# design.net
KiCad netlist of a schematic drawn in Altium Designer
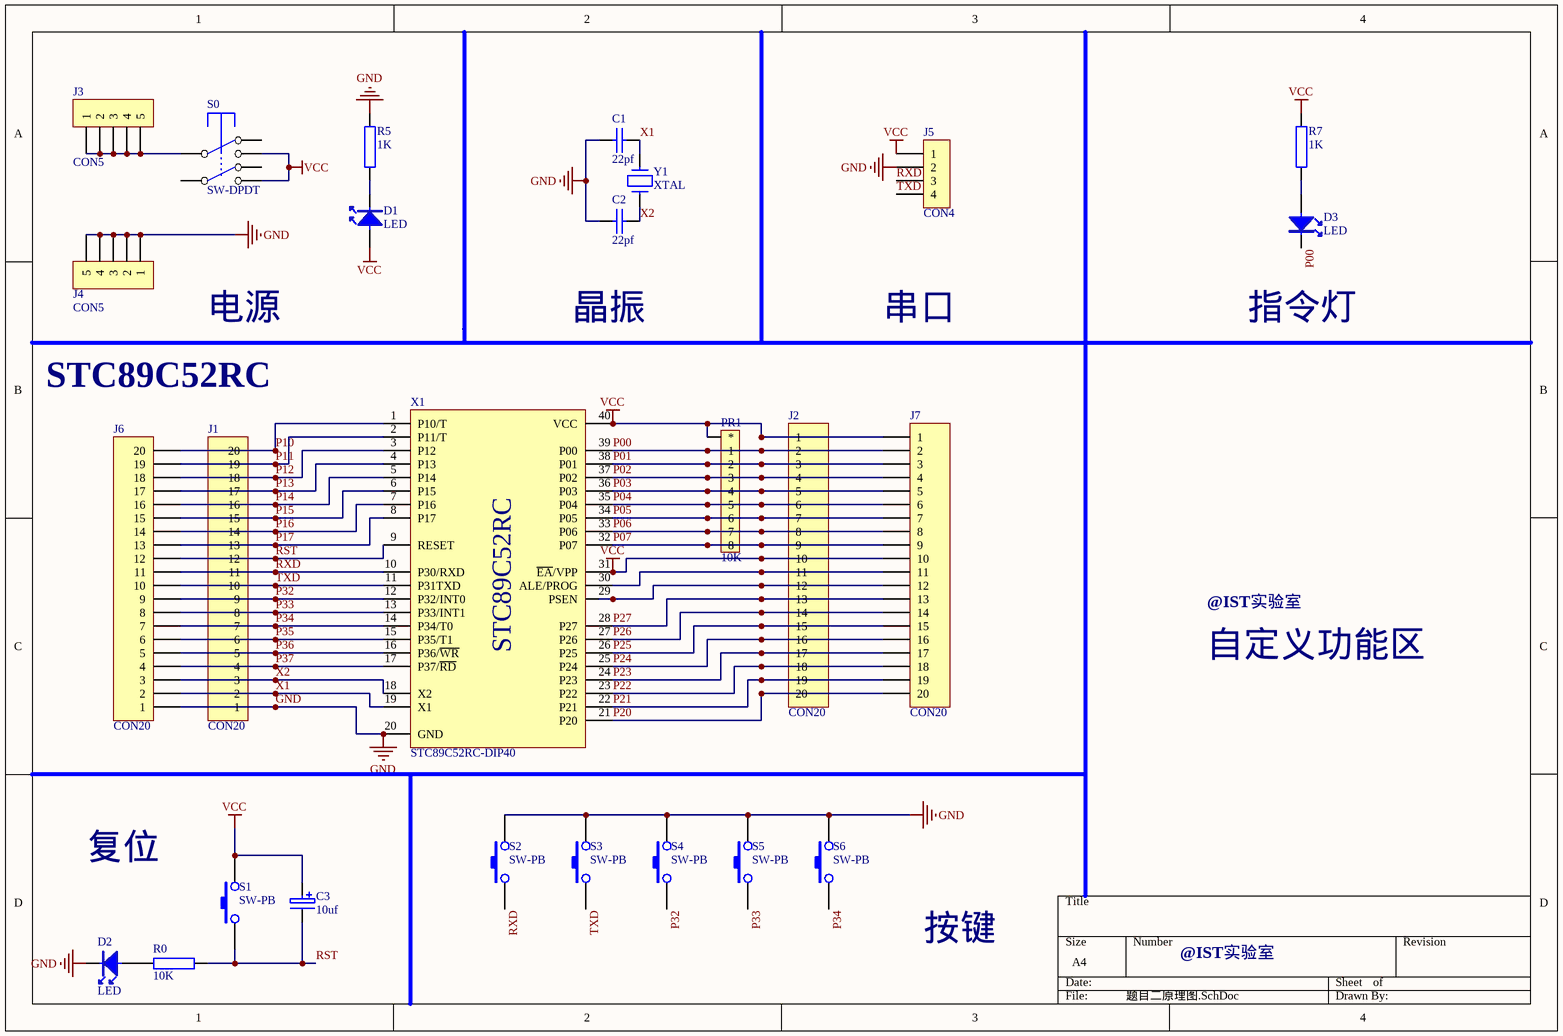
[diagram p0: 题目二原理图.SchDoc]

(export (version "E")
  (design (tool "Eeschema 10.0.6"))
  (components
    (comp (ref "C1") (value "22pf") (footprint "CAP2") (libsource (lib "51单片机集成库") (part "CAP1")))
    (comp (ref "C2") (value "22pf") (footprint "CAP2") (libsource (lib "51单片机集成库") (part "CAP1")))
    (comp (ref "C3") (value "10uf") (footprint "CAO1") (libsource (lib "51单片机集成库") (part "CAP3")))
    (comp (ref "D1") (value "LED") (footprint "LED2_B") (libsource (lib "51单片机集成库") (part "LED")))
    (comp (ref "D2") (value "LED") (footprint "LED2_B") (libsource (lib "51单片机集成库") (part "LED")))
    (comp (ref "D3") (value "LED") (footprint "LED2_B") (libsource (lib "51单片机集成库") (part "LED")))
    (comp (ref "J1")
      (value "CON20")
      (footprint "sip-20")
      (description "Connector")
      (libsource (lib "51单片机集成库") (part "CON20"))
    )
    (comp (ref "J2")
      (value "CON20")
      (footprint "sip-20")
      (description "Connector")
      (libsource (lib "") (part "CON20_1"))
    )
    (comp (ref "J3")
      (value "CON5")
      (footprint "sip-5")
      (description "Connector")
      (libsource (lib "") (part "CON5_1"))
    )
    (comp (ref "J4")
      (value "CON5")
      (footprint "sip-5")
      (description "Connector")
      (libsource (lib "51单片机集成库") (part "CON5"))
    )
    (comp (ref "J5")
      (value "CON4")
      (footprint "sip-4")
      (description "Connector")
      (libsource (lib "51单片机集成库") (part "CON4"))
    )
    (comp (ref "J6")
      (value "CON20")
      (footprint "sip-20")
      (description "Connector")
      (libsource (lib "51单片机集成库") (part "CON20"))
    )
    (comp (ref "J7")
      (value "CON20")
      (footprint "sip-20")
      (description "Connector")
      (libsource (lib "") (part "CON20_1"))
    )
    (comp (ref "PR1") (value "10K") (footprint "RP1") (libsource (lib "51单片机集成库") (part "PRES1")))
    (comp (ref "R0")
      (value "10K")
      (footprint "AXIAL0.4")
      (description "电阻")
      (libsource (lib "51单片机集成库") (part "RES"))
    )
    (comp (ref "R5")
      (value "1K")
      (footprint "AXIAL0.4")
      (description "电阻")
      (libsource (lib "51单片机集成库") (part "RES"))
    )
    (comp (ref "R7")
      (value "1K")
      (footprint "AXIAL0.4")
      (description "电阻")
      (libsource (lib "51单片机集成库") (part "RES"))
    )
    (comp (ref "S0") (value "SW-DPDT") (footprint "SWH7*7") (libsource (lib "51单片机集成库") (part "SW-DPDT")))
    (comp (ref "S1") (value "SW-PB") (footprint "SW6*6") (libsource (lib "51单片机集成库") (part "SW-PB")))
    (comp (ref "S2") (value "SW-PB") (footprint "SW6*6") (libsource (lib "51单片机集成库") (part "SW-PB")))
    (comp (ref "S3") (value "SW-PB") (footprint "SW6*6") (libsource (lib "51单片机集成库") (part "SW-PB")))
    (comp (ref "S4") (value "SW-PB") (footprint "SW6*6") (libsource (lib "51单片机集成库") (part "SW-PB")))
    (comp (ref "S5") (value "SW-PB") (footprint "SW6*6") (libsource (lib "51单片机集成库") (part "SW-PB")))
    (comp (ref "S6") (value "SW-PB") (footprint "SW6*6") (libsource (lib "51单片机集成库") (part "SW-PB")))
    (comp (ref "X1")
      (value "STC89C52RC-DIP40")
      (footprint "DIP-40")
      (libsource (lib "51单片机集成库") (part "STC89C52RC-DIP40"))
    )
    (comp (ref "Y1") (value "XTAL") (footprint "XTAL1") (libsource (lib "51单片机集成库") (part "CPY")))
  )
  (nets
    (net (code "1") (name "/P00") (class "Default")
      (node (ref "D3") (pin "2") (pinfunction "2_2") (pintype "passive"))
      (node (ref "J2") (pin "2") (pinfunction "2_2") (pintype "passive"))
      (node (ref "J7") (pin "2") (pinfunction "2_2") (pintype "passive"))
      (node (ref "PR1") (pin "2") (pinfunction "1_2") (pintype "passive"))
      (node (ref "X1") (pin "39") (pinfunction "P00_39") (pintype "passive"))
    )
    (net (code "2") (name "/P01") (class "Default")
      (node (ref "J2") (pin "3") (pinfunction "3_3") (pintype "passive"))
      (node (ref "J7") (pin "3") (pinfunction "3_3") (pintype "passive"))
      (node (ref "PR1") (pin "3") (pinfunction "2_3") (pintype "passive"))
      (node (ref "X1") (pin "38") (pinfunction "P01_38") (pintype "passive"))
    )
    (net (code "3") (name "/P02") (class "Default")
      (node (ref "J2") (pin "4") (pinfunction "4_4") (pintype "passive"))
      (node (ref "J7") (pin "4") (pinfunction "4_4") (pintype "passive"))
      (node (ref "PR1") (pin "4") (pinfunction "3_4") (pintype "passive"))
      (node (ref "X1") (pin "37") (pinfunction "P02_37") (pintype "passive"))
    )
    (net (code "4") (name "/P03") (class "Default")
      (node (ref "J2") (pin "5") (pinfunction "5_5") (pintype "passive"))
      (node (ref "J7") (pin "5") (pinfunction "5_5") (pintype "passive"))
      (node (ref "PR1") (pin "5") (pinfunction "4_5") (pintype "passive"))
      (node (ref "X1") (pin "36") (pinfunction "P03_36") (pintype "passive"))
    )
    (net (code "5") (name "/P04") (class "Default")
      (node (ref "J2") (pin "6") (pinfunction "6_6") (pintype "passive"))
      (node (ref "J7") (pin "6") (pinfunction "6_6") (pintype "passive"))
      (node (ref "PR1") (pin "6") (pinfunction "5_6") (pintype "passive"))
      (node (ref "X1") (pin "35") (pinfunction "P04_35") (pintype "passive"))
    )
    (net (code "6") (name "/P05") (class "Default")
      (node (ref "J2") (pin "7") (pinfunction "7_7") (pintype "passive"))
      (node (ref "J7") (pin "7") (pinfunction "7_7") (pintype "passive"))
      (node (ref "PR1") (pin "7") (pinfunction "6_7") (pintype "passive"))
      (node (ref "X1") (pin "34") (pinfunction "P05_34") (pintype "passive"))
    )
    (net (code "7") (name "/P06") (class "Default")
      (node (ref "J2") (pin "8") (pinfunction "8_8") (pintype "passive"))
      (node (ref "J7") (pin "8") (pinfunction "8_8") (pintype "passive"))
      (node (ref "PR1") (pin "8") (pinfunction "7_8") (pintype "passive"))
      (node (ref "X1") (pin "33") (pinfunction "P06_33") (pintype "passive"))
    )
    (net (code "8") (name "/P07") (class "Default")
      (node (ref "J2") (pin "9") (pinfunction "9_9") (pintype "passive"))
      (node (ref "J7") (pin "9") (pinfunction "9_9") (pintype "passive"))
      (node (ref "PR1") (pin "9") (pinfunction "8_9") (pintype "passive"))
      (node (ref "X1") (pin "32") (pinfunction "P07_32") (pintype "passive"))
    )
    (net (code "9") (name "/P10") (class "Default")
      (node (ref "J1") (pin "20") (pinfunction "20_20") (pintype "passive"))
      (node (ref "J6") (pin "20") (pinfunction "20_20") (pintype "passive"))
      (node (ref "X1") (pin "1") (pinfunction "P10/T_1") (pintype "passive"))
    )
    (net (code "10") (name "/P11") (class "Default")
      (node (ref "J1") (pin "19") (pinfunction "19_19") (pintype "passive"))
      (node (ref "J6") (pin "19") (pinfunction "19_19") (pintype "passive"))
      (node (ref "X1") (pin "2") (pinfunction "P11/T_2") (pintype "passive"))
    )
    (net (code "11") (name "/P12") (class "Default")
      (node (ref "J1") (pin "18") (pinfunction "18_18") (pintype "passive"))
      (node (ref "J6") (pin "18") (pinfunction "18_18") (pintype "passive"))
      (node (ref "X1") (pin "3") (pinfunction "P12_3") (pintype "passive"))
    )
    (net (code "12") (name "/P13") (class "Default")
      (node (ref "J1") (pin "17") (pinfunction "17_17") (pintype "passive"))
      (node (ref "J6") (pin "17") (pinfunction "17_17") (pintype "passive"))
      (node (ref "X1") (pin "4") (pinfunction "P13_4") (pintype "passive"))
    )
    (net (code "13") (name "/P14") (class "Default")
      (node (ref "J1") (pin "16") (pinfunction "16_16") (pintype "passive"))
      (node (ref "J6") (pin "16") (pinfunction "16_16") (pintype "passive"))
      (node (ref "X1") (pin "5") (pinfunction "P14_5") (pintype "passive"))
    )
    (net (code "14") (name "/P15") (class "Default")
      (node (ref "J1") (pin "15") (pinfunction "15_15") (pintype "passive"))
      (node (ref "J6") (pin "15") (pinfunction "15_15") (pintype "passive"))
      (node (ref "X1") (pin "6") (pinfunction "P15_6") (pintype "passive"))
    )
    (net (code "15") (name "/P16") (class "Default")
      (node (ref "J1") (pin "14") (pinfunction "14_14") (pintype "passive"))
      (node (ref "J6") (pin "14") (pinfunction "14_14") (pintype "passive"))
      (node (ref "X1") (pin "7") (pinfunction "P16_7") (pintype "passive"))
    )
    (net (code "16") (name "/P17") (class "Default")
      (node (ref "J1") (pin "13") (pinfunction "13_13") (pintype "passive"))
      (node (ref "J6") (pin "13") (pinfunction "13_13") (pintype "passive"))
      (node (ref "X1") (pin "8") (pinfunction "P17_8") (pintype "passive"))
    )
    (net (code "17") (name "/P20") (class "Default")
      (node (ref "J2") (pin "20") (pinfunction "20_20") (pintype "passive"))
      (node (ref "J7") (pin "20") (pinfunction "20_20") (pintype "passive"))
      (node (ref "X1") (pin "21") (pinfunction "P20_21") (pintype "passive"))
    )
    (net (code "18") (name "/P21") (class "Default")
      (node (ref "J2") (pin "19") (pinfunction "19_19") (pintype "passive"))
      (node (ref "J7") (pin "19") (pinfunction "19_19") (pintype "passive"))
      (node (ref "X1") (pin "22") (pinfunction "P21_22") (pintype "passive"))
    )
    (net (code "19") (name "/P22") (class "Default")
      (node (ref "J2") (pin "18") (pinfunction "18_18") (pintype "passive"))
      (node (ref "J7") (pin "18") (pinfunction "18_18") (pintype "passive"))
      (node (ref "X1") (pin "23") (pinfunction "P22_23") (pintype "passive"))
    )
    (net (code "20") (name "/P23") (class "Default")
      (node (ref "J2") (pin "17") (pinfunction "17_17") (pintype "passive"))
      (node (ref "J7") (pin "17") (pinfunction "17_17") (pintype "passive"))
      (node (ref "X1") (pin "24") (pinfunction "P23_24") (pintype "passive"))
    )
    (net (code "21") (name "/P24") (class "Default")
      (node (ref "J2") (pin "16") (pinfunction "16_16") (pintype "passive"))
      (node (ref "J7") (pin "16") (pinfunction "16_16") (pintype "passive"))
      (node (ref "X1") (pin "25") (pinfunction "P24_25") (pintype "passive"))
    )
    (net (code "22") (name "/P25") (class "Default")
      (node (ref "J2") (pin "15") (pinfunction "15_15") (pintype "passive"))
      (node (ref "J7") (pin "15") (pinfunction "15_15") (pintype "passive"))
      (node (ref "X1") (pin "26") (pinfunction "P25_26") (pintype "passive"))
    )
    (net (code "23") (name "/P26") (class "Default")
      (node (ref "J2") (pin "14") (pinfunction "14_14") (pintype "passive"))
      (node (ref "J7") (pin "14") (pinfunction "14_14") (pintype "passive"))
      (node (ref "X1") (pin "27") (pinfunction "P26_27") (pintype "passive"))
    )
    (net (code "24") (name "/P27") (class "Default")
      (node (ref "J2") (pin "13") (pinfunction "13_13") (pintype "passive"))
      (node (ref "J7") (pin "13") (pinfunction "13_13") (pintype "passive"))
      (node (ref "X1") (pin "28") (pinfunction "P27_28") (pintype "passive"))
    )
    (net (code "25") (name "/P32") (class "Default")
      (node (ref "J1") (pin "9") (pinfunction "9_9") (pintype "passive"))
      (node (ref "J6") (pin "9") (pinfunction "9_9") (pintype "passive"))
      (node (ref "S4") (pin "1") (pinfunction "1_1") (pintype "passive"))
      (node (ref "X1") (pin "12") (pinfunction "P32/INT0_12") (pintype "passive"))
    )
    (net (code "26") (name "/P33") (class "Default")
      (node (ref "J1") (pin "8") (pinfunction "8_8") (pintype "passive"))
      (node (ref "J6") (pin "8") (pinfunction "8_8") (pintype "passive"))
      (node (ref "S5") (pin "1") (pinfunction "1_1") (pintype "passive"))
      (node (ref "X1") (pin "13") (pinfunction "P33/INT1_13") (pintype "passive"))
    )
    (net (code "27") (name "/P34") (class "Default")
      (node (ref "J1") (pin "7") (pinfunction "7_7") (pintype "passive"))
      (node (ref "J6") (pin "7") (pinfunction "7_7") (pintype "passive"))
      (node (ref "S6") (pin "1") (pinfunction "1_1") (pintype "passive"))
      (node (ref "X1") (pin "14") (pinfunction "P34/T0_14") (pintype "passive"))
    )
    (net (code "28") (name "/P35") (class "Default")
      (node (ref "J1") (pin "6") (pinfunction "6_6") (pintype "passive"))
      (node (ref "J6") (pin "6") (pinfunction "6_6") (pintype "passive"))
      (node (ref "X1") (pin "15") (pinfunction "P35/T1_15") (pintype "passive"))
    )
    (net (code "29") (name "/P36") (class "Default")
      (node (ref "J1") (pin "5") (pinfunction "5_5") (pintype "passive"))
      (node (ref "J6") (pin "5") (pinfunction "5_5") (pintype "passive"))
      (node (ref "X1") (pin "16") (pinfunction "P36/~{WR}_16") (pintype "passive"))
    )
    (net (code "30") (name "/P37") (class "Default")
      (node (ref "J1") (pin "4") (pinfunction "4_4") (pintype "passive"))
      (node (ref "J6") (pin "4") (pinfunction "4_4") (pintype "passive"))
      (node (ref "X1") (pin "17") (pinfunction "P37/~{RD}_17") (pintype "passive"))
    )
    (net (code "31") (name "/RST") (class "Default")
      (node (ref "C3") (pin "2") (pintype "passive"))
      (node (ref "J1") (pin "12") (pinfunction "12_12") (pintype "passive"))
      (node (ref "J6") (pin "12") (pinfunction "12_12") (pintype "passive"))
      (node (ref "R0") (pin "2") (pinfunction "2_2") (pintype "passive"))
      (node (ref "S1") (pin "1") (pinfunction "1_1") (pintype "passive"))
      (node (ref "X1") (pin "9") (pinfunction "RESET_9") (pintype "passive"))
    )
    (net (code "32") (name "/RXD") (class "Default")
      (node (ref "J1") (pin "11") (pinfunction "11_11") (pintype "passive"))
      (node (ref "J5") (pin "3") (pinfunction "3_3") (pintype "passive"))
      (node (ref "J6") (pin "11") (pinfunction "11_11") (pintype "passive"))
      (node (ref "S2") (pin "1") (pinfunction "1_1") (pintype "passive"))
      (node (ref "X1") (pin "10") (pinfunction "P30/RXD_10") (pintype "passive"))
    )
    (net (code "33") (name "/TXD") (class "Default")
      (node (ref "J1") (pin "10") (pinfunction "10_10") (pintype "passive"))
      (node (ref "J5") (pin "4") (pinfunction "4_4") (pintype "passive"))
      (node (ref "J6") (pin "10") (pinfunction "10_10") (pintype "passive"))
      (node (ref "S3") (pin "1") (pinfunction "1_1") (pintype "passive"))
      (node (ref "X1") (pin "11") (pinfunction "P31TXD_11") (pintype "passive"))
    )
    (net (code "34") (name "/X1") (class "Default")
      (node (ref "C1") (pin "1") (pinfunction "1_1") (pintype "passive"))
      (node (ref "J1") (pin "2") (pinfunction "2_2") (pintype "passive"))
      (node (ref "J6") (pin "2") (pinfunction "2_2") (pintype "passive"))
      (node (ref "X1") (pin "19") (pinfunction "X1_19") (pintype "passive"))
      (node (ref "Y1") (pin "2") (pintype "passive"))
    )
    (net (code "35") (name "/X2") (class "Default")
      (node (ref "C2") (pin "1") (pinfunction "1_1") (pintype "passive"))
      (node (ref "J1") (pin "3") (pinfunction "3_3") (pintype "passive"))
      (node (ref "J6") (pin "3") (pinfunction "3_3") (pintype "passive"))
      (node (ref "X1") (pin "18") (pinfunction "X2_18") (pintype "passive"))
      (node (ref "Y1") (pin "1") (pintype "passive"))
    )
    (net (code "36") (name "GND") (class "Default")
      (node (ref "C1") (pin "2") (pinfunction "2_2") (pintype "passive"))
      (node (ref "C2") (pin "2") (pinfunction "2_2") (pintype "passive"))
      (node (ref "D2") (pin "2") (pinfunction "2_2") (pintype "passive"))
      (node (ref "J1") (pin "1") (pinfunction "1_1") (pintype "passive"))
      (node (ref "J4") (pin "1") (pinfunction "1_1") (pintype "passive"))
      (node (ref "J4") (pin "2") (pinfunction "2_2") (pintype "passive"))
      (node (ref "J4") (pin "3") (pinfunction "3_3") (pintype "passive"))
      (node (ref "J4") (pin "4") (pinfunction "4_4") (pintype "passive"))
      (node (ref "J4") (pin "5") (pinfunction "5_5") (pintype "passive"))
      (node (ref "J5") (pin "2") (pinfunction "2_2") (pintype "passive"))
      (node (ref "J6") (pin "1") (pinfunction "1_1") (pintype "passive"))
      (node (ref "R5") (pin "2") (pinfunction "2_2") (pintype "passive"))
      (node (ref "S2") (pin "2") (pinfunction "2_2") (pintype "passive"))
      (node (ref "S3") (pin "2") (pinfunction "2_2") (pintype "passive"))
      (node (ref "S4") (pin "2") (pinfunction "2_2") (pintype "passive"))
      (node (ref "S5") (pin "2") (pinfunction "2_2") (pintype "passive"))
      (node (ref "S6") (pin "2") (pinfunction "2_2") (pintype "passive"))
      (node (ref "X1") (pin "20") (pinfunction "GND_20") (pintype "passive"))
    )
    (net (code "37") (name "Net-(D1-Pad2)") (class "Default")
      (node (ref "D1") (pin "2") (pinfunction "2_2") (pintype "passive"))
      (node (ref "R5") (pin "1") (pinfunction "1_1") (pintype "passive"))
    )
    (net (code "38") (name "Net-(D2-Pad1)") (class "Default")
      (node (ref "D2") (pin "1") (pinfunction "1_1") (pintype "passive"))
      (node (ref "R0") (pin "1") (pinfunction "1_1") (pintype "passive"))
    )
    (net (code "39") (name "Net-(D3-Pad1)") (class "Default")
      (node (ref "D3") (pin "1") (pinfunction "1_1") (pintype "passive"))
      (node (ref "R7") (pin "1") (pinfunction "1_1") (pintype "passive"))
    )
    (net (code "40") (name "Net-(J3-Pad1)") (class "Default")
      (node (ref "J3") (pin "1") (pinfunction "1_1") (pintype "passive"))
      (node (ref "J3") (pin "2") (pinfunction "2_2") (pintype "passive"))
      (node (ref "J3") (pin "3") (pinfunction "3_3") (pintype "passive"))
      (node (ref "J3") (pin "4") (pinfunction "4_4") (pintype "passive"))
      (node (ref "J3") (pin "5") (pinfunction "5_5") (pintype "passive"))
      (node (ref "S0") (pin "2") (pinfunction "2_2") (pintype "passive"))
    )
    (net (code "41") (name "Net-(X1-ALE{slash}PROG)") (class "Default")
      (node (ref "J2") (pin "11") (pinfunction "11_11") (pintype "passive"))
      (node (ref "J7") (pin "11") (pinfunction "11_11") (pintype "passive"))
      (node (ref "X1") (pin "30") (pinfunction "ALE/PROG_30") (pintype "passive"))
    )
    (net (code "42") (name "Net-(X1-PSEN)") (class "Default")
      (node (ref "J2") (pin "12") (pinfunction "12_12") (pintype "passive"))
      (node (ref "J7") (pin "12") (pinfunction "12_12") (pintype "passive"))
      (node (ref "X1") (pin "29") (pinfunction "PSEN_29") (pintype "passive"))
    )
    (net (code "43") (name "VCC") (class "Default")
      (node (ref "C3") (pin "1") (pintype "passive"))
      (node (ref "D1") (pin "1") (pinfunction "1_1") (pintype "passive"))
      (node (ref "J2") (pin "1") (pinfunction "1_1") (pintype "passive"))
      (node (ref "J2") (pin "10") (pinfunction "10_10") (pintype "passive"))
      (node (ref "J5") (pin "1") (pinfunction "1_1") (pintype "passive"))
      (node (ref "J7") (pin "1") (pinfunction "1_1") (pintype "passive"))
      (node (ref "J7") (pin "10") (pinfunction "10_10") (pintype "passive"))
      (node (ref "PR1") (pin "1") (pinfunction "*_1") (pintype "passive"))
      (node (ref "R7") (pin "2") (pinfunction "2_2") (pintype "passive"))
      (node (ref "S0") (pin "3") (pinfunction "3_3") (pintype "passive"))
      (node (ref "S0") (pin "4") (pinfunction "4_4") (pintype "passive"))
      (node (ref "S1") (pin "2") (pinfunction "2_2") (pintype "passive"))
      (node (ref "X1") (pin "31") (pinfunction "~{EA}/VPP_31") (pintype "passive"))
      (node (ref "X1") (pin "40") (pinfunction "VCC_40") (pintype "passive"))
    )
    (net (code "44") (name "unconnected-(S0-Pad1)") (class "Default")
      (node (ref "S0") (pin "1") (pinfunction "1_1") (pintype "passive"))
    )
    (net (code "45") (name "unconnected-(S0-Pad5)") (class "Default")
      (node (ref "S0") (pin "5") (pinfunction "5_5") (pintype "passive"))
    )
    (net (code "46") (name "unconnected-(S0-Pad6)") (class "Default")
      (node (ref "S0") (pin "6") (pinfunction "6_6") (pintype "passive"))
    )
  )
)
